# RF_Transceiver_LMS6002_PLL_CLK.net
KiCad netlist of a schematic drawn in Altium Designer
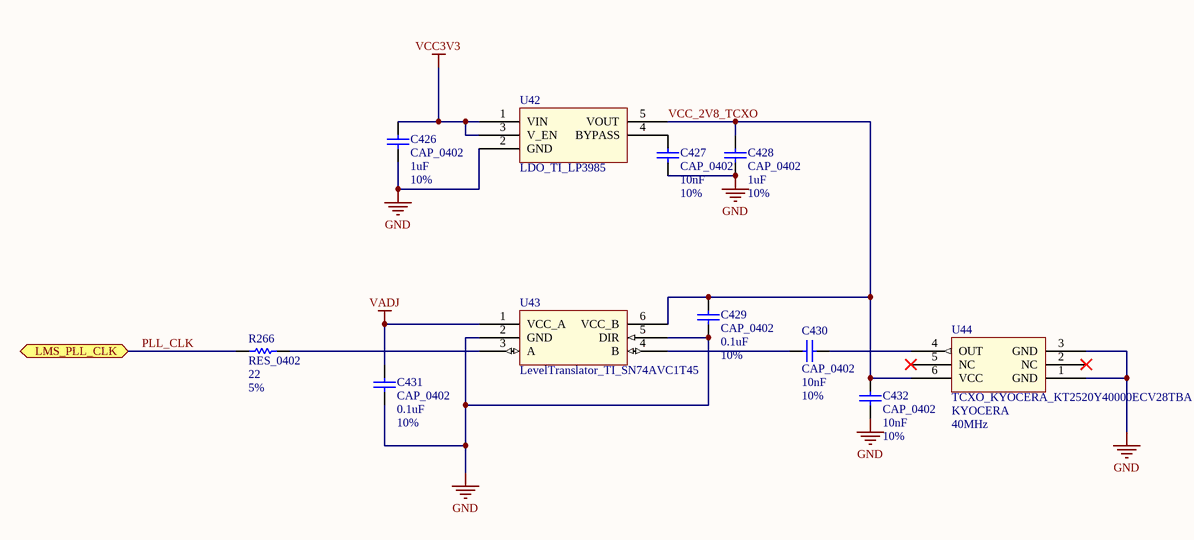
[diagram p0: RF_Transceiver_LMS6002_PLL_CLK.SchDoc]

(export (version "E")
  (design (tool "Eeschema 10.0.6"))
  (components
    (comp (ref "C426")
      (value "CAP_0402")
      (footprint "CAPC0402(1005)60_N")
      (description "1uF, ceramic, 10%, 6.3V, X5R, 0402")
      (fields
        (field (name "ALTIUM_VALUE") "1uF")
        (field (name "TOLERANCE") "10%")
        (field (name "PART NUMBER") "C1005X5R0J105K")
        (field (name "MANUFACTURER") "TDK Corporation")
      )
      (libsource (lib "COMRAD_Database") (part "CAP_0402"))
    )
    (comp (ref "C427")
      (value "CAP_0402")
      (footprint "CAPC0402(1005)60_N")
      (description "10000pF, ceramic, 10% 6.3V X5R, 0402")
      (fields
        (field (name "ALTIUM_VALUE") "10nF")
        (field (name "TOLERANCE") "10%")
        (field (name "PART NUMBER") "GRM155R60J103KA01D")
        (field (name "MANUFACTURER") "Murata Electronics North America")
      )
      (libsource (lib "COMRAD_Database") (part "CAP_0402"))
    )
    (comp (ref "C428")
      (value "CAP_0402")
      (footprint "CAPC0402(1005)60_N")
      (description "1uF, ceramic, 10%, 6.3V, X5R, 0402")
      (fields
        (field (name "ALTIUM_VALUE") "1uF")
        (field (name "TOLERANCE") "10%")
        (field (name "PART NUMBER") "C1005X5R0J105K")
        (field (name "MANUFACTURER") "TDK Corporation")
      )
      (libsource (lib "COMRAD_Database") (part "CAP_0402"))
    )
    (comp (ref "C429")
      (value "CAP_0402")
      (footprint "CAPC0402(1005)60_N")
      (description "0.1uf, ceramic, 10%, 6.3V, X5R, 0402")
      (fields
        (field (name "ALTIUM_VALUE") "0.1uF")
        (field (name "TOLERANCE") "10%")
        (field (name "PART NUMBER") "C1005X5R0J104K")
        (field (name "MANUFACTURER") "TDK Corporation")
      )
      (libsource (lib "COMRAD_Database") (part "CAP_0402"))
    )
    (comp (ref "C430")
      (value "CAP_0402")
      (footprint "CAPC0402(1005)60_N")
      (description "10000pF, ceramic, 10% 6.3V X5R, 0402")
      (fields
        (field (name "ALTIUM_VALUE") "10nF")
        (field (name "TOLERANCE") "10%")
        (field (name "PART NUMBER") "GRM155R60J103KA01D")
        (field (name "MANUFACTURER") "Murata Electronics North America")
      )
      (libsource (lib "COMRAD_Database") (part "CAP_0402"))
    )
    (comp (ref "C431")
      (value "CAP_0402")
      (footprint "CAPC0402(1005)60_N")
      (description "0.1uf, ceramic, 10%, 6.3V, X5R, 0402")
      (fields
        (field (name "ALTIUM_VALUE") "0.1uF")
        (field (name "TOLERANCE") "10%")
        (field (name "PART NUMBER") "C1005X5R0J104K")
        (field (name "MANUFACTURER") "TDK Corporation")
      )
      (libsource (lib "COMRAD_Database") (part "CAP_0402"))
    )
    (comp (ref "C432")
      (value "CAP_0402")
      (footprint "CAPC0402(1005)60_N")
      (description "10000pF, ceramic, 10% 6.3V X5R, 0402")
      (fields
        (field (name "ALTIUM_VALUE") "10nF")
        (field (name "TOLERANCE") "10%")
        (field (name "PART NUMBER") "GRM155R60J103KA01D")
        (field (name "MANUFACTURER") "Murata Electronics North America")
      )
      (libsource (lib "COMRAD_Database") (part "CAP_0402"))
    )
    (comp (ref "R266")
      (value "RES_0402")
      (footprint "RESC0402(1005)_N")
      (description "RES 22 OHM 1/10W 5% 0402 SMD")
      (fields
        (field (name "ALTIUM_VALUE") "22")
        (field (name "TOLERANCE") "5%")
        (field (name "PART NUMBER") "ERJ-2GEJ220X")
        (field (name "MANUFACTURER") "Panasonic Electronic Components")
      )
      (libsource (lib "COMRAD_Database") (part "RES_0402"))
    )
    (comp (ref "U42")
      (value "LDO_TI_LP3985")
      (footprint "LDO_TI_LP3985_SOT23-5")
      (description "LDO_TI_LP3985,150mA,CMOS, IC REG LDO 2.8V .15A SOT-23-5")
      (fields
        (field (name "PART NUMBER") "LP3985IM5-2.8/NOPB")
        (field (name "MANUFACTURER") "Texas Instruments")
      )
      (libsource (lib "COMRAD_Database") (part "LDO_TI_LP3985"))
    )
    (comp (ref "U43")
      (value "LevelTranslator_TI_SN74AVC1T45")
      (footprint "LevelTranslator_TI_SN74AVC1T45 _SC70-6")
      (description "Level Translator, IC BUS TRANSCVR TRI-ST SC70-6")
      (fields
        (field (name "PART NUMBER") "SN74AVC1T45DCKR")
        (field (name "MANUFACTURER") "Texas Instruments")
      )
      (libsource (lib "COMRAD_Database") (part "LevelTranslator_TI_SN74AVC1T45"))
    )
    (comp (ref "U44")
      (value "TCXO_KYOCERA_KT2520Y40000ECV28TBA")
      (footprint "TCXO_KYOCERA_KT2520Y40000ECV28TBA_PCB-6PIN")
      (description "TCXO_KYOCERA_KT2520Y40000ECV28TBA,40MHz,2.8V")
      (fields
        (field (name "PART NUMBER") "KT2520Y40000ECV28TBA")
        (field (name "MANUFACTURER") "KYOCERA")
        (field (name "ALTIUM_VALUE") "40MHz")
      )
      (libsource (lib "COMRAD_Database") (part "TCXO_KYOCERA_KT2520Y40000ECV28TBA"))
    )
  )
  (nets
    (net (code "1") (name "/PLL_CLK") (class "Default")
      (node (ref "R266") (pin "1") (pinfunction "1_1") (pintype "passive"))
    )
    (net (code "2") (name "/VCC_2V8_TCXO") (class "Default")
      (node (ref "C428") (pin "2") (pinfunction "2_2") (pintype "passive"))
      (node (ref "C429") (pin "2") (pinfunction "2_2") (pintype "passive"))
      (node (ref "C432") (pin "2") (pinfunction "2_2") (pintype "passive"))
      (node (ref "U42") (pin "5") (pinfunction "VOUT_5") (pintype "power_in"))
      (node (ref "U43") (pin "6") (pinfunction "VCC_B_6") (pintype "power_in"))
      (node (ref "U44") (pin "6") (pinfunction "VCC_6") (pintype "power_in"))
    )
    (net (code "3") (name "GND") (class "Default")
      (node (ref "C426") (pin "1") (pinfunction "1_1") (pintype "passive"))
      (node (ref "C427") (pin "1") (pinfunction "1_1") (pintype "passive"))
      (node (ref "C428") (pin "1") (pinfunction "1_1") (pintype "passive"))
      (node (ref "C429") (pin "1") (pinfunction "1_1") (pintype "passive"))
      (node (ref "C431") (pin "2") (pinfunction "2_2") (pintype "passive"))
      (node (ref "C432") (pin "1") (pinfunction "1_1") (pintype "passive"))
      (node (ref "U42") (pin "2") (pinfunction "GND_2") (pintype "passive"))
      (node (ref "U43") (pin "2") (pinfunction "GND_2") (pintype "power_in"))
      (node (ref "U43") (pin "5") (pinfunction "DIR_5") (pintype "input"))
      (node (ref "U44") (pin "1") (pinfunction "GND_1") (pintype "power_in"))
      (node (ref "U44") (pin "3") (pinfunction "GND_3") (pintype "power_in"))
    )
    (net (code "4") (name "Net-(U42-BYPASS)") (class "Default")
      (node (ref "C427") (pin "2") (pinfunction "2_2") (pintype "passive"))
      (node (ref "U42") (pin "4") (pinfunction "BYPASS_4") (pintype "passive"))
    )
    (net (code "5") (name "Net-(U43-A)") (class "Default")
      (node (ref "R266") (pin "2") (pinfunction "2_2") (pintype "passive"))
      (node (ref "U43") (pin "3") (pinfunction "A_3") (pintype "bidirectional"))
    )
    (net (code "6") (name "Net-(U43-B)") (class "Default")
      (node (ref "C430") (pin "1") (pinfunction "1_1") (pintype "passive"))
      (node (ref "U43") (pin "4") (pinfunction "B_4") (pintype "bidirectional"))
    )
    (net (code "7") (name "Net-(U44-OUT)") (class "Default")
      (node (ref "C430") (pin "2") (pinfunction "2_2") (pintype "passive"))
      (node (ref "U44") (pin "4") (pinfunction "OUT_4") (pintype "output"))
    )
    (net (code "8") (name "VADJ") (class "Default")
      (node (ref "C431") (pin "1") (pinfunction "1_1") (pintype "passive"))
      (node (ref "U43") (pin "1") (pinfunction "VCC_A_1") (pintype "power_in"))
    )
    (net (code "9") (name "VCC3V3") (class "Default")
      (node (ref "C426") (pin "2") (pinfunction "2_2") (pintype "passive"))
      (node (ref "U42") (pin "1") (pinfunction "VIN_1") (pintype "power_in"))
      (node (ref "U42") (pin "3") (pinfunction "V_EN_3") (pintype "passive"))
    )
    (net (code "10") (name "unconnected-(U44-NC-Pad2)") (class "Default")
      (node (ref "U44") (pin "2") (pinfunction "NC_2") (pintype "passive+no_connect"))
    )
    (net (code "11") (name "unconnected-(U44-NC-Pad5)") (class "Default")
      (node (ref "U44") (pin "5") (pinfunction "NC_5") (pintype "passive+no_connect"))
    )
  )
)
